# G020X.net
KiCad netlist of a schematic drawn in EAGLE
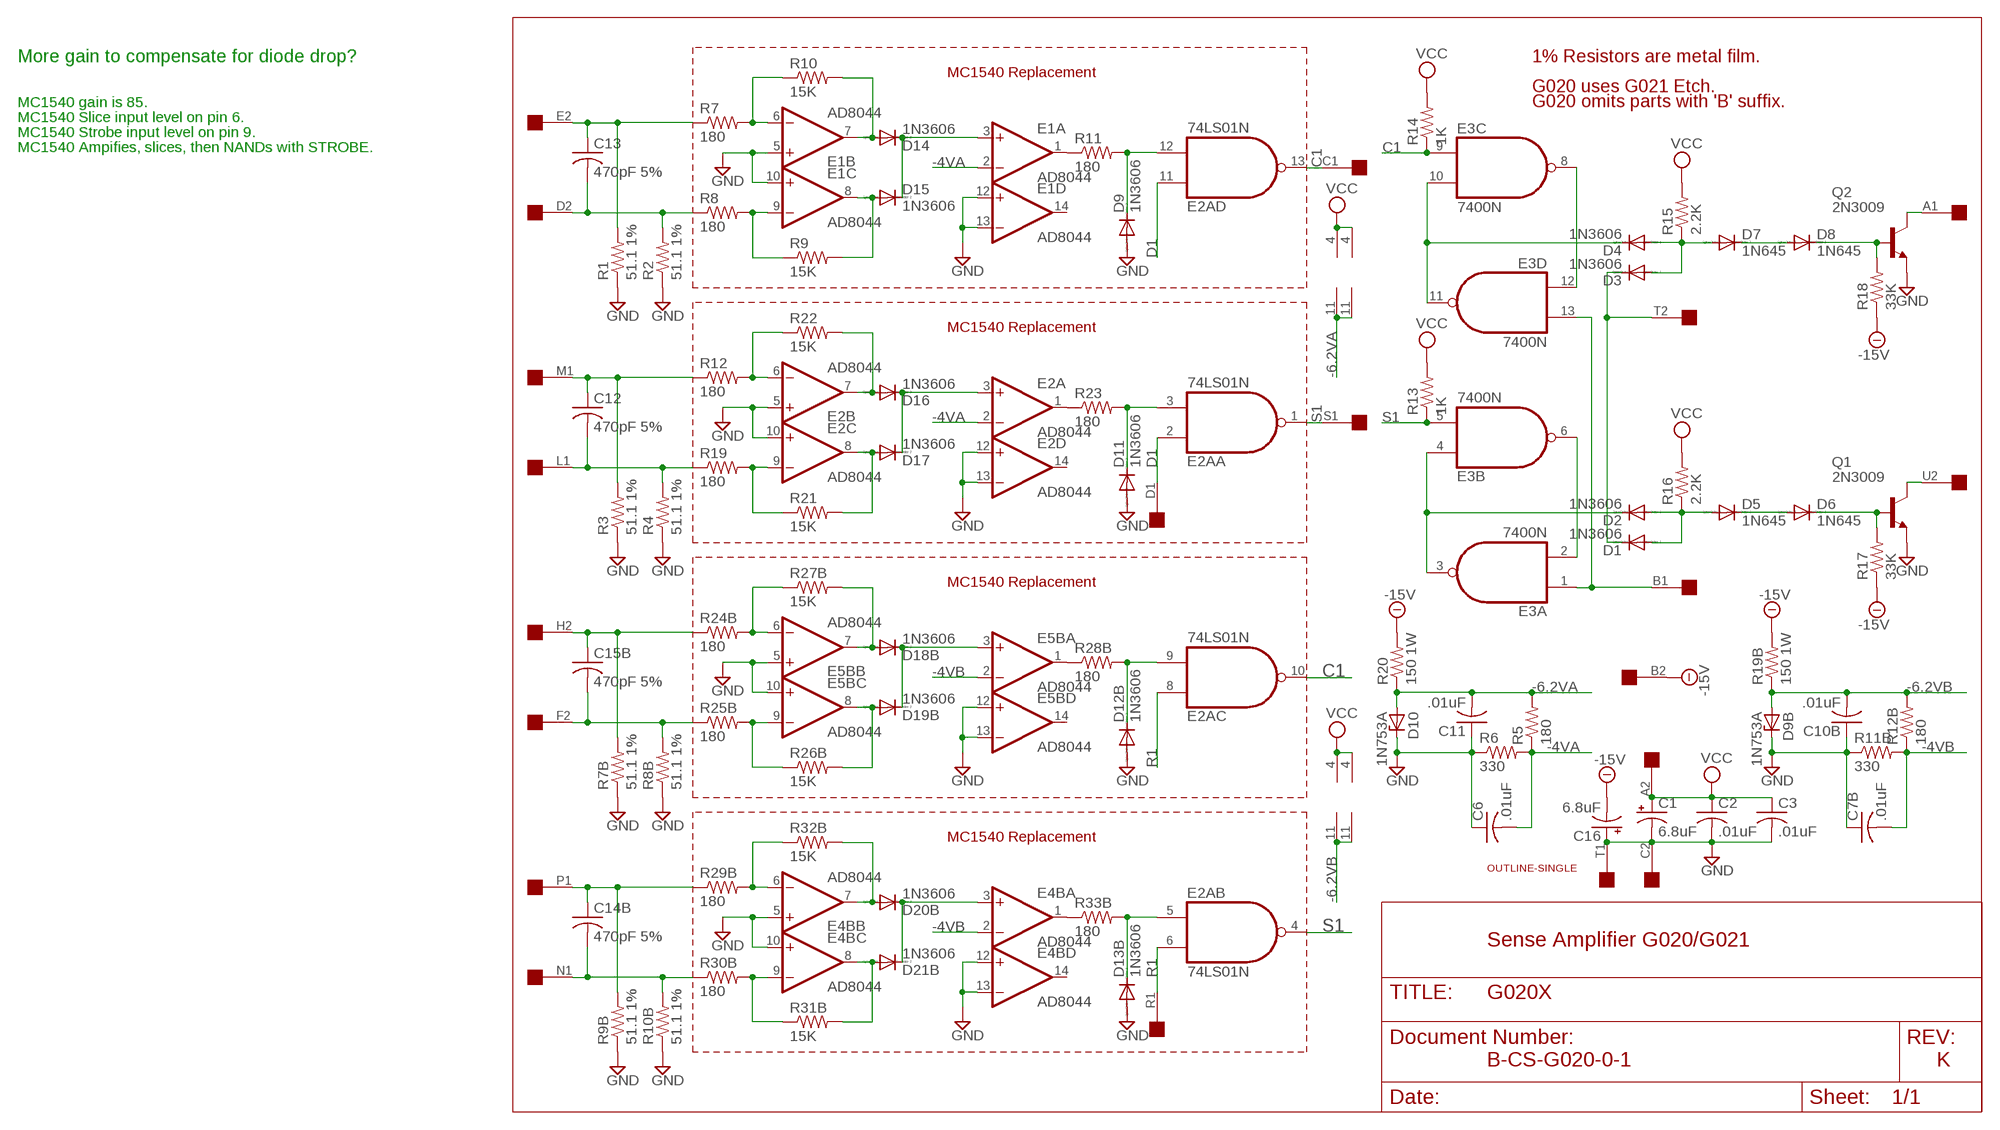
[diagram p0: schematic, sheet 1]

(export (version "E")
  (design (tool "Eeschema 10.0.6"))
  (components
    (comp (ref "C1")
      (value "6.8uF")
      (footprint "eagle-import:E12-8")
      (libsource (lib "eagle-import") (part "CPOL-USE20-8AXIAL"))
    )
    (comp (ref "C2")
      (value ".01uF")
      (footprint "eagle-import:C050-025X075")
      (libsource (lib "eagle-import") (part "C-US050-025X075"))
    )
    (comp (ref "C3")
      (value ".01uF")
      (footprint "eagle-import:C050-025X075")
      (libsource (lib "eagle-import") (part "C-US050-025X075"))
    )
    (comp (ref "C6")
      (value ".01uF")
      (footprint "eagle-import:C050-025X075")
      (libsource (lib "eagle-import") (part "C-US050-025X075"))
    )
    (comp (ref "C7B")
      (value ".01uF")
      (footprint "eagle-import:C050-025X075")
      (libsource (lib "eagle-import") (part "C-US050-025X075"))
    )
    (comp (ref "C10B")
      (value ".01uF")
      (footprint "eagle-import:C050-025X075")
      (libsource (lib "eagle-import") (part "C-US050-025X075"))
    )
    (comp (ref "C11")
      (value ".01uF")
      (footprint "eagle-import:C050-025X075")
      (libsource (lib "eagle-import") (part "C-US050-025X075"))
    )
    (comp (ref "C12")
      (value "470pF 5%")
      (footprint "eagle-import:C050-025X075")
      (libsource (lib "eagle-import") (part "C-US050-025X075"))
    )
    (comp (ref "C13")
      (value "470pF 5%")
      (footprint "eagle-import:C050-025X075")
      (libsource (lib "eagle-import") (part "C-US050-025X075"))
    )
    (comp (ref "C14B")
      (value "470pF 5%")
      (footprint "eagle-import:C050-025X075")
      (libsource (lib "eagle-import") (part "C-US050-025X075"))
    )
    (comp (ref "C15B")
      (value "470pF 5%")
      (footprint "eagle-import:C050-025X075")
      (libsource (lib "eagle-import") (part "C-US050-025X075"))
    )
    (comp (ref "C16")
      (value "6.8uF")
      (footprint "eagle-import:E12-8")
      (libsource (lib "eagle-import") (part "CPOL-USE20-8AXIAL"))
    )
    (comp (ref "D1")
      (value "1N3606")
      (footprint "eagle-import:DO35-10")
      (libsource (lib "eagle-import") (part "1N4148DO35-10"))
    )
    (comp (ref "D2")
      (value "1N3606")
      (footprint "eagle-import:DO35-10")
      (libsource (lib "eagle-import") (part "1N4148DO35-10"))
    )
    (comp (ref "D3")
      (value "1N3606")
      (footprint "eagle-import:DO35-10")
      (libsource (lib "eagle-import") (part "1N4148DO35-10"))
    )
    (comp (ref "D4")
      (value "1N3606")
      (footprint "eagle-import:DO35-10")
      (libsource (lib "eagle-import") (part "1N4148DO35-10"))
    )
    (comp (ref "D5")
      (value "1N645")
      (footprint "eagle-import:DO35-10")
      (libsource (lib "eagle-import") (part "1N4148DO35-10"))
    )
    (comp (ref "D6")
      (value "1N645")
      (footprint "eagle-import:DO35-10")
      (libsource (lib "eagle-import") (part "1N4148DO35-10"))
    )
    (comp (ref "D7")
      (value "1N645")
      (footprint "eagle-import:DO35-10")
      (libsource (lib "eagle-import") (part "1N4148DO35-10"))
    )
    (comp (ref "D8")
      (value "1N645")
      (footprint "eagle-import:DO35-10")
      (libsource (lib "eagle-import") (part "1N4148DO35-10"))
    )
    (comp (ref "D9")
      (value "1N3606")
      (footprint "eagle-import:DO35-10")
      (libsource (lib "eagle-import") (part "1N4148DO35-10"))
    )
    (comp (ref "D9B")
      (value "1N753A")
      (footprint "eagle-import:DO35Z10")
      (libsource (lib "eagle-import") (part "ZENER-DIODEDO35Z10"))
    )
    (comp (ref "D10")
      (value "1N753A")
      (footprint "eagle-import:DO35Z10")
      (libsource (lib "eagle-import") (part "ZENER-DIODEDO35Z10"))
    )
    (comp (ref "D11")
      (value "1N3606")
      (footprint "eagle-import:DO35-10")
      (libsource (lib "eagle-import") (part "1N4148DO35-10"))
    )
    (comp (ref "D12B")
      (value "1N3606")
      (footprint "eagle-import:DO35-10")
      (libsource (lib "eagle-import") (part "1N4148DO35-10"))
    )
    (comp (ref "D13B")
      (value "1N3606")
      (footprint "eagle-import:DO35-10")
      (libsource (lib "eagle-import") (part "1N4148DO35-10"))
    )
    (comp (ref "D14")
      (value "1N3606")
      (footprint "eagle-import:DO35-10")
      (libsource (lib "eagle-import") (part "1N4148DO35-10"))
    )
    (comp (ref "D15")
      (value "1N3606")
      (footprint "eagle-import:DO35-10")
      (libsource (lib "eagle-import") (part "1N4148DO35-10"))
    )
    (comp (ref "D16")
      (value "1N3606")
      (footprint "eagle-import:DO35-10")
      (libsource (lib "eagle-import") (part "1N4148DO35-10"))
    )
    (comp (ref "D17")
      (value "1N3606")
      (footprint "eagle-import:DO35-10")
      (libsource (lib "eagle-import") (part "1N4148DO35-10"))
    )
    (comp (ref "D18B")
      (value "1N3606")
      (footprint "eagle-import:DO35-10")
      (libsource (lib "eagle-import") (part "1N4148DO35-10"))
    )
    (comp (ref "D19B")
      (value "1N3606")
      (footprint "eagle-import:DO35-10")
      (libsource (lib "eagle-import") (part "1N4148DO35-10"))
    )
    (comp (ref "D20B")
      (value "1N3606")
      (footprint "eagle-import:DO35-10")
      (libsource (lib "eagle-import") (part "1N4148DO35-10"))
    )
    (comp (ref "D21B")
      (value "1N3606")
      (footprint "eagle-import:DO35-10")
      (libsource (lib "eagle-import") (part "1N4148DO35-10"))
    )
    (comp (ref "E1")
      (value "AD8044")
      (footprint "eagle-import:DIL14")
      (libsource (lib "eagle-import") (part "4AMP_P4+11N"))
    )
    (comp (ref "E2")
      (value "AD8044")
      (footprint "eagle-import:DIL14")
      (libsource (lib "eagle-import") (part "4AMP_P4+11N"))
    )
    (comp (ref "E2A")
      (value "74LS01N")
      (footprint "eagle-import:DIL14")
      (libsource (lib "eagle-import") (part "7401NLS"))
    )
    (comp (ref "E3")
      (value "7400N")
      (footprint "eagle-import:DIL14")
      (libsource (lib "eagle-import") (part "7400N"))
    )
    (comp (ref "E4B")
      (value "AD8044")
      (footprint "eagle-import:DIL14")
      (libsource (lib "eagle-import") (part "4AMP_P4+11N"))
    )
    (comp (ref "E5B")
      (value "AD8044")
      (footprint "eagle-import:DIL14")
      (libsource (lib "eagle-import") (part "4AMP_P4+11N"))
    )
    (comp (ref "Q1")
      (value "2N3009")
      (footprint "eagle-import:TO5")
      (libsource (lib "eagle-import") (part "2N2219"))
    )
    (comp (ref "Q2")
      (value "2N3009")
      (footprint "eagle-import:TO5")
      (libsource (lib "eagle-import") (part "2N2219"))
    )
    (comp (ref "R1")
      (value "51.1 1%")
      (footprint "eagle-import:0207_10")
      (libsource (lib "eagle-import") (part "R-US_0207/10"))
    )
    (comp (ref "R2")
      (value "51.1 1%")
      (footprint "eagle-import:0207_10")
      (libsource (lib "eagle-import") (part "R-US_0207/10"))
    )
    (comp (ref "R3")
      (value "51.1 1%")
      (footprint "eagle-import:0207_10")
      (libsource (lib "eagle-import") (part "R-US_0207/10"))
    )
    (comp (ref "R4")
      (value "51.1 1%")
      (footprint "eagle-import:0207_10")
      (libsource (lib "eagle-import") (part "R-US_0207/10"))
    )
    (comp (ref "R5")
      (value "180")
      (footprint "eagle-import:0207_10")
      (libsource (lib "eagle-import") (part "R-US_0207/10"))
    )
    (comp (ref "R6")
      (value "330")
      (footprint "eagle-import:0207_10")
      (libsource (lib "eagle-import") (part "R-US_0207/10"))
    )
    (comp (ref "R7")
      (value "180")
      (footprint "eagle-import:0207_10")
      (libsource (lib "eagle-import") (part "R-US_0207/10"))
    )
    (comp (ref "R7B")
      (value "51.1 1%")
      (footprint "eagle-import:0207_10")
      (libsource (lib "eagle-import") (part "R-US_0207/10"))
    )
    (comp (ref "R8")
      (value "180")
      (footprint "eagle-import:0207_10")
      (libsource (lib "eagle-import") (part "R-US_0207/10"))
    )
    (comp (ref "R8B")
      (value "51.1 1%")
      (footprint "eagle-import:0207_10")
      (libsource (lib "eagle-import") (part "R-US_0207/10"))
    )
    (comp (ref "R9")
      (value "15K")
      (footprint "eagle-import:0207_10")
      (libsource (lib "eagle-import") (part "R-US_0207/10"))
    )
    (comp (ref "R9B")
      (value "51.1 1%")
      (footprint "eagle-import:0207_10")
      (libsource (lib "eagle-import") (part "R-US_0207/10"))
    )
    (comp (ref "R10")
      (value "15K")
      (footprint "eagle-import:0207_10")
      (libsource (lib "eagle-import") (part "R-US_0207/10"))
    )
    (comp (ref "R10B")
      (value "51.1 1%")
      (footprint "eagle-import:0207_10")
      (libsource (lib "eagle-import") (part "R-US_0207/10"))
    )
    (comp (ref "R11")
      (value "180")
      (footprint "eagle-import:0207_10")
      (libsource (lib "eagle-import") (part "R-US_0207/10"))
    )
    (comp (ref "R11B")
      (value "330")
      (footprint "eagle-import:0207_10")
      (libsource (lib "eagle-import") (part "R-US_0207/10"))
    )
    (comp (ref "R12")
      (value "180")
      (footprint "eagle-import:0207_10")
      (libsource (lib "eagle-import") (part "R-US_0207/10"))
    )
    (comp (ref "R12B")
      (value "180")
      (footprint "eagle-import:0207_10")
      (libsource (lib "eagle-import") (part "R-US_0207/10"))
    )
    (comp (ref "R13")
      (value "1K")
      (footprint "eagle-import:0207_10")
      (libsource (lib "eagle-import") (part "R-US_0207/10"))
    )
    (comp (ref "R14")
      (value "1K")
      (footprint "eagle-import:0207_10")
      (libsource (lib "eagle-import") (part "R-US_0207/10"))
    )
    (comp (ref "R15")
      (value "2.2K")
      (footprint "eagle-import:0207_10")
      (libsource (lib "eagle-import") (part "R-US_0207/10"))
    )
    (comp (ref "R16")
      (value "2.2K")
      (footprint "eagle-import:0207_10")
      (libsource (lib "eagle-import") (part "R-US_0207/10"))
    )
    (comp (ref "R17")
      (value "33K")
      (footprint "eagle-import:0207_10")
      (libsource (lib "eagle-import") (part "R-US_0207/10"))
    )
    (comp (ref "R18")
      (value "33K")
      (footprint "eagle-import:0207_10")
      (libsource (lib "eagle-import") (part "R-US_0207/10"))
    )
    (comp (ref "R19")
      (value "180")
      (footprint "eagle-import:0207_10")
      (libsource (lib "eagle-import") (part "R-US_0207/10"))
    )
    (comp (ref "R19B")
      (value "150 1W")
      (footprint "eagle-import:0414_20")
      (libsource (lib "eagle-import") (part "R-US_0414/20"))
    )
    (comp (ref "R20")
      (value "150 1W")
      (footprint "eagle-import:0414_20")
      (libsource (lib "eagle-import") (part "R-US_0414/20"))
    )
    (comp (ref "R21")
      (value "15K")
      (footprint "eagle-import:0207_10")
      (libsource (lib "eagle-import") (part "R-US_0207/10"))
    )
    (comp (ref "R22")
      (value "15K")
      (footprint "eagle-import:0207_10")
      (libsource (lib "eagle-import") (part "R-US_0207/10"))
    )
    (comp (ref "R23")
      (value "180")
      (footprint "eagle-import:0207_10")
      (libsource (lib "eagle-import") (part "R-US_0207/10"))
    )
    (comp (ref "R24B")
      (value "180")
      (footprint "eagle-import:0207_10")
      (libsource (lib "eagle-import") (part "R-US_0207/10"))
    )
    (comp (ref "R25B")
      (value "180")
      (footprint "eagle-import:0207_10")
      (libsource (lib "eagle-import") (part "R-US_0207/10"))
    )
    (comp (ref "R26B")
      (value "15K")
      (footprint "eagle-import:0207_10")
      (libsource (lib "eagle-import") (part "R-US_0207/10"))
    )
    (comp (ref "R27B")
      (value "15K")
      (footprint "eagle-import:0207_10")
      (libsource (lib "eagle-import") (part "R-US_0207/10"))
    )
    (comp (ref "R28B")
      (value "180")
      (footprint "eagle-import:0207_10")
      (libsource (lib "eagle-import") (part "R-US_0207/10"))
    )
    (comp (ref "R29B")
      (value "180")
      (footprint "eagle-import:0207_10")
      (libsource (lib "eagle-import") (part "R-US_0207/10"))
    )
    (comp (ref "R30B")
      (value "180")
      (footprint "eagle-import:0207_10")
      (libsource (lib "eagle-import") (part "R-US_0207/10"))
    )
    (comp (ref "R31B")
      (value "15K")
      (footprint "eagle-import:0207_10")
      (libsource (lib "eagle-import") (part "R-US_0207/10"))
    )
    (comp (ref "R32B")
      (value "15K")
      (footprint "eagle-import:0207_10")
      (libsource (lib "eagle-import") (part "R-US_0207/10"))
    )
    (comp (ref "R33B")
      (value "180")
      (footprint "eagle-import:0207_10")
      (libsource (lib "eagle-import") (part "R-US_0207/10"))
    )
    (comp (ref "U$1")
      (value "SINGLE")
      (footprint "eagle-import:EDGE-CON2")
      (libsource (lib "eagle-import") (part "SINGLE"))
    )
    (comp (ref "U$2")
      (value "OUTLINE-SINGLE")
      (footprint "eagle-import:SINGLE")
      (libsource (lib "eagle-import") (part "OUTLINE-SINGLE"))
    )
  )
  (nets
    (net (code "1") (name "-15V") (class "Default")
      (node (ref "C16") (pin "-") (pinfunction "-_-") (pintype "passive"))
      (node (ref "R17") (pin "1") (pinfunction "1_1") (pintype "passive"))
      (node (ref "R18") (pin "1") (pinfunction "1_1") (pintype "passive"))
      (node (ref "R19B") (pin "2") (pinfunction "2_2") (pintype "passive"))
      (node (ref "R20") (pin "2") (pinfunction "2_2") (pintype "passive"))
      (node (ref "U$1") (pin "B2") (pinfunction "1_B2") (pintype "bidirectional"))
    )
    (net (code "2") (name "/-4VA") (class "Default")
      (node (ref "C6") (pin "2") (pinfunction "2_2") (pintype "passive"))
      (node (ref "E1") (pin "2") (pinfunction "-IN_2") (pintype "input"))
      (node (ref "E2") (pin "2") (pinfunction "-IN_2") (pintype "input"))
      (node (ref "R5") (pin "1") (pinfunction "1_1") (pintype "passive"))
      (node (ref "R6") (pin "2") (pinfunction "2_2") (pintype "passive"))
    )
    (net (code "3") (name "/-4VB") (class "Default")
      (node (ref "C7B") (pin "2") (pinfunction "2_2") (pintype "passive"))
      (node (ref "E4B") (pin "2") (pinfunction "-IN_2") (pintype "input"))
      (node (ref "E5B") (pin "2") (pinfunction "-IN_2") (pintype "input"))
      (node (ref "R11B") (pin "2") (pinfunction "2_2") (pintype "passive"))
      (node (ref "R12B") (pin "1") (pinfunction "1_1") (pintype "passive"))
    )
    (net (code "4") (name "/-6.2VA") (class "Default")
      (node (ref "C11") (pin "2") (pinfunction "2_2") (pintype "passive"))
      (node (ref "D10") (pin "A") (pinfunction "A_A") (pintype "passive"))
      (node (ref "E1") (pin "11") (pinfunction "V-_11") (pintype "power_in"))
      (node (ref "E2") (pin "11") (pinfunction "V-_11") (pintype "power_in"))
      (node (ref "R20") (pin "1") (pinfunction "1_1") (pintype "passive"))
      (node (ref "R5") (pin "2") (pinfunction "2_2") (pintype "passive"))
    )
    (net (code "5") (name "/-6.2VB") (class "Default")
      (node (ref "C10B") (pin "2") (pinfunction "2_2") (pintype "passive"))
      (node (ref "D9B") (pin "A") (pinfunction "A_A") (pintype "passive"))
      (node (ref "E4B") (pin "11") (pinfunction "V-_11") (pintype "power_in"))
      (node (ref "E5B") (pin "11") (pinfunction "V-_11") (pintype "power_in"))
      (node (ref "R12B") (pin "2") (pinfunction "2_2") (pintype "passive"))
      (node (ref "R19B") (pin "1") (pinfunction "1_1") (pintype "passive"))
    )
    (net (code "6") (name "/C1") (class "Default")
      (node (ref "E2A") (pin "10") (pinfunction "O_10") (pintype "open_collector"))
      (node (ref "E2A") (pin "13") (pinfunction "O_13") (pintype "open_collector"))
      (node (ref "E3") (pin "9") (pinfunction "I0_9") (pintype "input"))
      (node (ref "R14") (pin "1") (pinfunction "1_1") (pintype "passive"))
      (node (ref "U$1") (pin "C1") (pinfunction "1_C1") (pintype "bidirectional"))
    )
    (net (code "7") (name "/D1") (class "Default")
      (node (ref "E2A") (pin "11") (pinfunction "I0_11") (pintype "input"))
      (node (ref "E2A") (pin "2") (pinfunction "I0_2") (pintype "input"))
      (node (ref "U$1") (pin "D1") (pinfunction "1_D1") (pintype "bidirectional"))
    )
    (net (code "8") (name "/R1") (class "Default")
      (node (ref "E2A") (pin "6") (pinfunction "I1_6") (pintype "input"))
      (node (ref "E2A") (pin "8") (pinfunction "I0_8") (pintype "input"))
      (node (ref "U$1") (pin "R1") (pinfunction "1_R1") (pintype "bidirectional"))
    )
    (net (code "9") (name "/S1") (class "Default")
      (node (ref "E2A") (pin "1") (pinfunction "O_1") (pintype "open_collector"))
      (node (ref "E2A") (pin "4") (pinfunction "O_4") (pintype "open_collector"))
      (node (ref "E3") (pin "5") (pinfunction "I1_5") (pintype "input"))
      (node (ref "R13") (pin "1") (pinfunction "1_1") (pintype "passive"))
      (node (ref "U$1") (pin "S1") (pinfunction "1_S1") (pintype "bidirectional"))
    )
    (net (code "10") (name "GND") (class "Default")
      (node (ref "C1") (pin "-") (pinfunction "-_-") (pintype "passive"))
      (node (ref "C10B") (pin "1") (pinfunction "1_1") (pintype "passive"))
      (node (ref "C11") (pin "1") (pinfunction "1_1") (pintype "passive"))
      (node (ref "C16") (pin "+") (pinfunction "+_+") (pintype "passive"))
      (node (ref "C2") (pin "2") (pinfunction "2_2") (pintype "passive"))
      (node (ref "C3") (pin "2") (pinfunction "2_2") (pintype "passive"))
      (node (ref "C6") (pin "1") (pinfunction "1_1") (pintype "passive"))
      (node (ref "C7B") (pin "1") (pinfunction "1_1") (pintype "passive"))
      (node (ref "D10") (pin "C") (pinfunction "C_C") (pintype "passive"))
      (node (ref "D11") (pin "A") (pinfunction "A_A") (pintype "passive"))
      (node (ref "D12B") (pin "A") (pinfunction "A_A") (pintype "passive"))
      (node (ref "D13B") (pin "A") (pinfunction "A_A") (pintype "passive"))
      (node (ref "D9") (pin "A") (pinfunction "A_A") (pintype "passive"))
      (node (ref "D9B") (pin "C") (pinfunction "C_C") (pintype "passive"))
      (node (ref "E1") (pin "10") (pinfunction "+IN_10") (pintype "input"))
      (node (ref "E1") (pin "12") (pinfunction "+IN_12") (pintype "input"))
      (node (ref "E1") (pin "13") (pinfunction "-IN_13") (pintype "input"))
      (node (ref "E1") (pin "5") (pinfunction "+IN_5") (pintype "input"))
      (node (ref "E2") (pin "10") (pinfunction "+IN_10") (pintype "input"))
      (node (ref "E2") (pin "12") (pinfunction "+IN_12") (pintype "input"))
      (node (ref "E2") (pin "13") (pinfunction "-IN_13") (pintype "input"))
      (node (ref "E2") (pin "5") (pinfunction "+IN_5") (pintype "input"))
      (node (ref "E4B") (pin "10") (pinfunction "+IN_10") (pintype "input"))
      (node (ref "E4B") (pin "12") (pinfunction "+IN_12") (pintype "input"))
      (node (ref "E4B") (pin "13") (pinfunction "-IN_13") (pintype "input"))
      (node (ref "E4B") (pin "5") (pinfunction "+IN_5") (pintype "input"))
      (node (ref "E5B") (pin "10") (pinfunction "+IN_10") (pintype "input"))
      (node (ref "E5B") (pin "12") (pinfunction "+IN_12") (pintype "input"))
      (node (ref "E5B") (pin "13") (pinfunction "-IN_13") (pintype "input"))
      (node (ref "E5B") (pin "5") (pinfunction "+IN_5") (pintype "input"))
      (node (ref "Q1") (pin "1") (pinfunction "E_1") (pintype "passive"))
      (node (ref "Q2") (pin "1") (pinfunction "E_1") (pintype "passive"))
      (node (ref "R1") (pin "1") (pinfunction "1_1") (pintype "passive"))
      (node (ref "R10B") (pin "1") (pinfunction "1_1") (pintype "passive"))
      (node (ref "R11B") (pin "1") (pinfunction "1_1") (pintype "passive"))
      (node (ref "R2") (pin "1") (pinfunction "1_1") (pintype "passive"))
      (node (ref "R3") (pin "1") (pinfunction "1_1") (pintype "passive"))
      (node (ref "R4") (pin "1") (pinfunction "1_1") (pintype "passive"))
      (node (ref "R6") (pin "1") (pinfunction "1_1") (pintype "passive"))
      (node (ref "R7B") (pin "1") (pinfunction "1_1") (pintype "passive"))
      (node (ref "R8B") (pin "1") (pinfunction "1_1") (pintype "passive"))
      (node (ref "R9B") (pin "1") (pinfunction "1_1") (pintype "passive"))
      (node (ref "U$1") (pin "C2") (pinfunction "1_C2") (pintype "bidirectional"))
      (node (ref "U$1") (pin "T1") (pinfunction "1_T1") (pintype "bidirectional"))
    )
    (net (code "11") (name "Net-(D1-PadA)") (class "Default")
      (node (ref "D1") (pin "A") (pinfunction "A_A") (pintype "passive"))
      (node (ref "D2") (pin "A") (pinfunction "A_A") (pintype "passive"))
      (node (ref "D5") (pin "A") (pinfunction "A_A") (pintype "passive"))
      (node (ref "R16") (pin "1") (pinfunction "1_1") (pintype "passive"))
    )
    (net (code "12") (name "Net-(D3-PadA)") (class "Default")
      (node (ref "D3") (pin "A") (pinfunction "A_A") (pintype "passive"))
      (node (ref "D4") (pin "A") (pinfunction "A_A") (pintype "passive"))
      (node (ref "D7") (pin "A") (pinfunction "A_A") (pintype "passive"))
      (node (ref "R15") (pin "1") (pinfunction "1_1") (pintype "passive"))
    )
    (net (code "13") (name "Net-(D5-PadC)") (class "Default")
      (node (ref "D5") (pin "C") (pinfunction "C_C") (pintype "passive"))
      (node (ref "D6") (pin "A") (pinfunction "A_A") (pintype "passive"))
    )
    (net (code "14") (name "Net-(D7-PadC)") (class "Default")
      (node (ref "D7") (pin "C") (pinfunction "C_C") (pintype "passive"))
      (node (ref "D8") (pin "A") (pinfunction "A_A") (pintype "passive"))
    )
    (net (code "15") (name "Net-(E1A-+IN)") (class "Default")
      (node (ref "D14") (pin "C") (pinfunction "C_C") (pintype "passive"))
      (node (ref "D15") (pin "C") (pinfunction "C_C") (pintype "passive"))
      (node (ref "E1") (pin "3") (pinfunction "+IN_3") (pintype "input"))
    )
    (net (code "16") (name "Net-(E1A-OUT)") (class "Default")
      (node (ref "E1") (pin "1") (pinfunction "OUT_1") (pintype "output"))
      (node (ref "R11") (pin "1") (pinfunction "1_1") (pintype "passive"))
    )
    (net (code "17") (name "Net-(E1B--IN)") (class "Default")
      (node (ref "E1") (pin "6") (pinfunction "-IN_6") (pintype "input"))
      (node (ref "R10") (pin "1") (pinfunction "1_1") (pintype "passive"))
      (node (ref "R7") (pin "2") (pinfunction "2_2") (pintype "passive"))
    )
    (net (code "18") (name "Net-(E1B-OUT)") (class "Default")
      (node (ref "D14") (pin "A") (pinfunction "A_A") (pintype "passive"))
      (node (ref "E1") (pin "7") (pinfunction "OUT_7") (pintype "output"))
      (node (ref "R10") (pin "2") (pinfunction "2_2") (pintype "passive"))
    )
    (net (code "19") (name "Net-(E1C--IN)") (class "Default")
      (node (ref "E1") (pin "9") (pinfunction "-IN_9") (pintype "input"))
      (node (ref "R8") (pin "2") (pinfunction "2_2") (pintype "passive"))
      (node (ref "R9") (pin "1") (pinfunction "1_1") (pintype "passive"))
    )
    (net (code "20") (name "Net-(E1C-OUT)") (class "Default")
      (node (ref "D15") (pin "A") (pinfunction "A_A") (pintype "passive"))
      (node (ref "E1") (pin "8") (pinfunction "OUT_8") (pintype "output"))
      (node (ref "R9") (pin "2") (pinfunction "2_2") (pintype "passive"))
    )
    (net (code "21") (name "Net-(E2A-+IN)") (class "Default")
      (node (ref "D16") (pin "C") (pinfunction "C_C") (pintype "passive"))
      (node (ref "D17") (pin "C") (pinfunction "C_C") (pintype "passive"))
      (node (ref "E2") (pin "3") (pinfunction "+IN_3") (pintype "input"))
    )
    (net (code "22") (name "Net-(E2A-OUT)") (class "Default")
      (node (ref "E2") (pin "1") (pinfunction "OUT_1") (pintype "output"))
      (node (ref "R23") (pin "1") (pinfunction "1_1") (pintype "passive"))
    )
    (net (code "23") (name "Net-(E2AA-I1)") (class "Default")
      (node (ref "D11") (pin "C") (pinfunction "C_C") (pintype "passive"))
      (node (ref "E2A") (pin "3") (pinfunction "I1_3") (pintype "input"))
      (node (ref "R23") (pin "2") (pinfunction "2_2") (pintype "passive"))
    )
    (net (code "24") (name "Net-(E2AB-I0)") (class "Default")
      (node (ref "D13B") (pin "C") (pinfunction "C_C") (pintype "passive"))
      (node (ref "E2A") (pin "5") (pinfunction "I0_5") (pintype "input"))
      (node (ref "R33B") (pin "2") (pinfunction "2_2") (pintype "passive"))
    )
    (net (code "25") (name "Net-(E2AC-I1)") (class "Default")
      (node (ref "D12B") (pin "C") (pinfunction "C_C") (pintype "passive"))
      (node (ref "E2A") (pin "9") (pinfunction "I1_9") (pintype "input"))
      (node (ref "R28B") (pin "2") (pinfunction "2_2") (pintype "passive"))
    )
    (net (code "26") (name "Net-(E2AD-I1)") (class "Default")
      (node (ref "D9") (pin "C") (pinfunction "C_C") (pintype "passive"))
      (node (ref "E2A") (pin "12") (pinfunction "I1_12") (pintype "input"))
      (node (ref "R11") (pin "2") (pinfunction "2_2") (pintype "passive"))
    )
    (net (code "27") (name "Net-(E2B--IN)") (class "Default")
      (node (ref "E2") (pin "6") (pinfunction "-IN_6") (pintype "input"))
      (node (ref "R12") (pin "2") (pinfunction "2_2") (pintype "passive"))
      (node (ref "R22") (pin "1") (pinfunction "1_1") (pintype "passive"))
    )
    (net (code "28") (name "Net-(E2B-OUT)") (class "Default")
      (node (ref "D16") (pin "A") (pinfunction "A_A") (pintype "passive"))
      (node (ref "E2") (pin "7") (pinfunction "OUT_7") (pintype "output"))
      (node (ref "R22") (pin "2") (pinfunction "2_2") (pintype "passive"))
    )
    (net (code "29") (name "Net-(E2C--IN)") (class "Default")
      (node (ref "E2") (pin "9") (pinfunction "-IN_9") (pintype "input"))
      (node (ref "R19") (pin "2") (pinfunction "2_2") (pintype "passive"))
      (node (ref "R21") (pin "1") (pinfunction "1_1") (pintype "passive"))
    )
    (net (code "30") (name "Net-(E2C-OUT)") (class "Default")
      (node (ref "D17") (pin "A") (pinfunction "A_A") (pintype "passive"))
      (node (ref "E2") (pin "8") (pinfunction "OUT_8") (pintype "output"))
      (node (ref "R21") (pin "2") (pinfunction "2_2") (pintype "passive"))
    )
    (net (code "31") (name "Net-(E3A-I0)") (class "Default")
      (node (ref "E3") (pin "1") (pinfunction "I0_1") (pintype "input"))
      (node (ref "E3") (pin "13") (pinfunction "I1_13") (pintype "input"))
      (node (ref "U$1") (pin "B1") (pinfunction "1_B1") (pintype "bidirectional"))
    )
    (net (code "32") (name "Net-(E3A-I1)") (class "Default")
      (node (ref "E3") (pin "2") (pinfunction "I1_2") (pintype "input"))
      (node (ref "E3") (pin "6") (pinfunction "O_6") (pintype "output"))
    )
    (net (code "33") (name "Net-(E3A-O)") (class "Default")
      (node (ref "D2") (pin "C") (pinfunction "C_C") (pintype "passive"))
      (node (ref "E3") (pin "3") (pinfunction "O_3") (pintype "output"))
      (node (ref "E3") (pin "4") (pinfunction "I0_4") (pintype "input"))
    )
    (net (code "34") (name "Net-(E3C-I1)") (class "Default")
      (node (ref "D4") (pin "C") (pinfunction "C_C") (pintype "passive"))
      (node (ref "E3") (pin "10") (pinfunction "I1_10") (pintype "input"))
      (node (ref "E3") (pin "11") (pinfunction "O_11") (pintype "output"))
    )
    (net (code "35") (name "Net-(E3C-O)") (class "Default")
      (node (ref "E3") (pin "12") (pinfunction "I0_12") (pintype "input"))
      (node (ref "E3") (pin "8") (pinfunction "O_8") (pintype "output"))
    )
    (net (code "36") (name "Net-(E4BA-+IN)") (class "Default")
      (node (ref "D20B") (pin "C") (pinfunction "C_C") (pintype "passive"))
      (node (ref "D21B") (pin "C") (pinfunction "C_C") (pintype "passive"))
      (node (ref "E4B") (pin "3") (pinfunction "+IN_3") (pintype "input"))
    )
    (net (code "37") (name "Net-(E4BA-OUT)") (class "Default")
      (node (ref "E4B") (pin "1") (pinfunction "OUT_1") (pintype "output"))
      (node (ref "R33B") (pin "1") (pinfunction "1_1") (pintype "passive"))
    )
    (net (code "38") (name "Net-(E4BB--IN)") (class "Default")
      (node (ref "E4B") (pin "6") (pinfunction "-IN_6") (pintype "input"))
      (node (ref "R29B") (pin "2") (pinfunction "2_2") (pintype "passive"))
      (node (ref "R32B") (pin "1") (pinfunction "1_1") (pintype "passive"))
    )
    (net (code "39") (name "Net-(E4BB-OUT)") (class "Default")
      (node (ref "D20B") (pin "A") (pinfunction "A_A") (pintype "passive"))
      (node (ref "E4B") (pin "7") (pinfunction "OUT_7") (pintype "output"))
      (node (ref "R32B") (pin "2") (pinfunction "2_2") (pintype "passive"))
    )
    (net (code "40") (name "Net-(E4BC--IN)") (class "Default")
      (node (ref "E4B") (pin "9") (pinfunction "-IN_9") (pintype "input"))
      (node (ref "R30B") (pin "2") (pinfunction "2_2") (pintype "passive"))
      (node (ref "R31B") (pin "1") (pinfunction "1_1") (pintype "passive"))
    )
    (net (code "41") (name "Net-(E4BC-OUT)") (class "Default")
      (node (ref "D21B") (pin "A") (pinfunction "A_A") (pintype "passive"))
      (node (ref "E4B") (pin "8") (pinfunction "OUT_8") (pintype "output"))
      (node (ref "R31B") (pin "2") (pinfunction "2_2") (pintype "passive"))
    )
    (net (code "42") (name "Net-(E5BA-+IN)") (class "Default")
      (node (ref "D18B") (pin "C") (pinfunction "C_C") (pintype "passive"))
      (node (ref "D19B") (pin "C") (pinfunction "C_C") (pintype "passive"))
      (node (ref "E5B") (pin "3") (pinfunction "+IN_3") (pintype "input"))
    )
    (net (code "43") (name "Net-(E5BA-OUT)") (class "Default")
      (node (ref "E5B") (pin "1") (pinfunction "OUT_1") (pintype "output"))
      (node (ref "R28B") (pin "1") (pinfunction "1_1") (pintype "passive"))
    )
    (net (code "44") (name "Net-(E5BB--IN)") (class "Default")
      (node (ref "E5B") (pin "6") (pinfunction "-IN_6") (pintype "input"))
      (node (ref "R24B") (pin "2") (pinfunction "2_2") (pintype "passive"))
      (node (ref "R27B") (pin "1") (pinfunction "1_1") (pintype "passive"))
    )
    (net (code "45") (name "Net-(E5BB-OUT)") (class "Default")
      (node (ref "D18B") (pin "A") (pinfunction "A_A") (pintype "passive"))
      (node (ref "E5B") (pin "7") (pinfunction "OUT_7") (pintype "output"))
      (node (ref "R27B") (pin "2") (pinfunction "2_2") (pintype "passive"))
    )
    (net (code "46") (name "Net-(E5BC--IN)") (class "Default")
      (node (ref "E5B") (pin "9") (pinfunction "-IN_9") (pintype "input"))
      (node (ref "R25B") (pin "2") (pinfunction "2_2") (pintype "passive"))
      (node (ref "R26B") (pin "1") (pinfunction "1_1") (pintype "passive"))
    )
    (net (code "47") (name "Net-(E5BC-OUT)") (class "Default")
      (node (ref "D19B") (pin "A") (pinfunction "A_A") (pintype "passive"))
      (node (ref "E5B") (pin "8") (pinfunction "OUT_8") (pintype "output"))
      (node (ref "R26B") (pin "2") (pinfunction "2_2") (pintype "passive"))
    )
    (net (code "48") (name "Net-(Q1-B)") (class "Default")
      (node (ref "D6") (pin "C") (pinfunction "C_C") (pintype "passive"))
      (node (ref "Q1") (pin "2") (pinfunction "B_2") (pintype "passive"))
      (node (ref "R17") (pin "2") (pinfunction "2_2") (pintype "passive"))
    )
    (net (code "49") (name "Net-(Q1-C)") (class "Default")
      (node (ref "Q1") (pin "3") (pinfunction "C_3") (pintype "passive"))
      (node (ref "U$1") (pin "U2") (pinfunction "1_U2") (pintype "bidirectional"))
    )
    (net (code "50") (name "Net-(Q2-B)") (class "Default")
      (node (ref "D8") (pin "C") (pinfunction "C_C") (pintype "passive"))
      (node (ref "Q2") (pin "2") (pinfunction "B_2") (pintype "passive"))
      (node (ref "R18") (pin "2") (pinfunction "2_2") (pintype "passive"))
    )
    (net (code "51") (name "Net-(Q2-C)") (class "Default")
      (node (ref "Q2") (pin "3") (pinfunction "C_3") (pintype "passive"))
      (node (ref "U$1") (pin "A1") (pinfunction "1_A1") (pintype "bidirectional"))
    )
    (net (code "52") (name "Net-(U$1AF-1)") (class "Default")
      (node (ref "D1") (pin "C") (pinfunction "C_C") (pintype "passive"))
      (node (ref "D3") (pin "C") (pinfunction "C_C") (pintype "passive"))
      (node (ref "U$1") (pin "T2") (pinfunction "1_T2") (pintype "bidirectional"))
    )
    (net (code "53") (name "Net-(U$1H-1)") (class "Default")
      (node (ref "C13") (pin "2") (pinfunction "2_2") (pintype "passive"))
      (node (ref "R2") (pin "2") (pinfunction "2_2") (pintype "passive"))
      (node (ref "R8") (pin "1") (pinfunction "1_1") (pintype "passive"))
      (node (ref "U$1") (pin "D2") (pinfunction "1_D2") (pintype "bidirectional"))
    )
    (net (code "54") (name "Net-(U$1J-1)") (class "Default")
      (node (ref "C13") (pin "1") (pinfunction "1_1") (pintype "passive"))
      (node (ref "R1") (pin "2") (pinfunction "2_2") (pintype "passive"))
      (node (ref "R7") (pin "1") (pinfunction "1_1") (pintype "passive"))
      (node (ref "U$1") (pin "E2") (pinfunction "1_E2") (pintype "bidirectional"))
    )
    (net (code "55") (name "Net-(U$1L-1)") (class "Default")
      (node (ref "C15B") (pin "2") (pinfunction "2_2") (pintype "passive"))
      (node (ref "R25B") (pin "1") (pinfunction "1_1") (pintype "passive"))
      (node (ref "R8B") (pin "2") (pinfunction "2_2") (pintype "passive"))
      (node (ref "U$1") (pin "F2") (pinfunction "1_F2") (pintype "bidirectional"))
    )
    (net (code "56") (name "Net-(U$1N-1)") (class "Default")
      (node (ref "C15B") (pin "1") (pinfunction "1_1") (pintype "passive"))
      (node (ref "R24B") (pin "1") (pinfunction "1_1") (pintype "passive"))
      (node (ref "R7B") (pin "2") (pinfunction "2_2") (pintype "passive"))
      (node (ref "U$1") (pin "H2") (pinfunction "1_H2") (pintype "bidirectional"))
    )
    (net (code "57") (name "Net-(U$1S-1)") (class "Default")
      (node (ref "C12") (pin "2") (pinfunction "2_2") (pintype "passive"))
      (node (ref "R19") (pin "1") (pinfunction "1_1") (pintype "passive"))
      (node (ref "R4") (pin "2") (pinfunction "2_2") (pintype "passive"))
      (node (ref "U$1") (pin "L1") (pinfunction "1_L1") (pintype "bidirectional"))
    )
    (net (code "58") (name "Net-(U$1U-1)") (class "Default")
      (node (ref "C12") (pin "1") (pinfunction "1_1") (pintype "passive"))
      (node (ref "R12") (pin "1") (pinfunction "1_1") (pintype "passive"))
      (node (ref "R3") (pin "2") (pinfunction "2_2") (pintype "passive"))
      (node (ref "U$1") (pin "M1") (pinfunction "1_M1") (pintype "bidirectional"))
    )
    (net (code "59") (name "Net-(U$1W-1)") (class "Default")
      (node (ref "C14B") (pin "2") (pinfunction "2_2") (pintype "passive"))
      (node (ref "R10B") (pin "2") (pinfunction "2_2") (pintype "passive"))
      (node (ref "R30B") (pin "1") (pinfunction "1_1") (pintype "passive"))
      (node (ref "U$1") (pin "N1") (pinfunction "1_N1") (pintype "bidirectional"))
    )
    (net (code "60") (name "Net-(U$1Y-1)") (class "Default")
      (node (ref "C14B") (pin "1") (pinfunction "1_1") (pintype "passive"))
      (node (ref "R29B") (pin "1") (pinfunction "1_1") (pintype "passive"))
      (node (ref "R9B") (pin "2") (pinfunction "2_2") (pintype "passive"))
      (node (ref "U$1") (pin "P1") (pinfunction "1_P1") (pintype "bidirectional"))
    )
    (net (code "61") (name "VCC") (class "Default")
      (node (ref "C1") (pin "+") (pinfunction "+_+") (pintype "passive"))
      (node (ref "C2") (pin "1") (pinfunction "1_1") (pintype "passive"))
      (node (ref "C3") (pin "1") (pinfunction "1_1") (pintype "passive"))
      (node (ref "E1") (pin "4") (pinfunction "V+_4") (pintype "power_in"))
      (node (ref "E2") (pin "4") (pinfunction "V+_4") (pintype "power_in"))
      (node (ref "E4B") (pin "4") (pinfunction "V+_4") (pintype "power_in"))
      (node (ref "E5B") (pin "4") (pinfunction "V+_4") (pintype "power_in"))
      (node (ref "R13") (pin "2") (pinfunction "2_2") (pintype "passive"))
      (node (ref "R14") (pin "2") (pinfunction "2_2") (pintype "passive"))
      (node (ref "R15") (pin "2") (pinfunction "2_2") (pintype "passive"))
      (node (ref "R16") (pin "2") (pinfunction "2_2") (pintype "passive"))
      (node (ref "U$1") (pin "A2") (pinfunction "1_A2") (pintype "bidirectional"))
    )
    (net (code "62") (name "unconnected-(E1D-OUT-Pad14)") (class "Default")
      (node (ref "E1") (pin "14") (pinfunction "OUT_14") (pintype "output"))
    )
    (net (code "63") (name "unconnected-(E2D-OUT-Pad14)") (class "Default")
      (node (ref "E2") (pin "14") (pinfunction "OUT_14") (pintype "output"))
    )
    (net (code "64") (name "unconnected-(E4BD-OUT-Pad14)") (class "Default")
      (node (ref "E4B") (pin "14") (pinfunction "OUT_14") (pintype "output"))
    )
    (net (code "65") (name "unconnected-(E5BD-OUT-Pad14)") (class "Default")
      (node (ref "E5B") (pin "14") (pinfunction "OUT_14") (pintype "output"))
    )
  )
)
